# SCH_NFC-Card-Justin_2025-02-16.net
KiCad netlist of a schematic drawn in EasyEDA
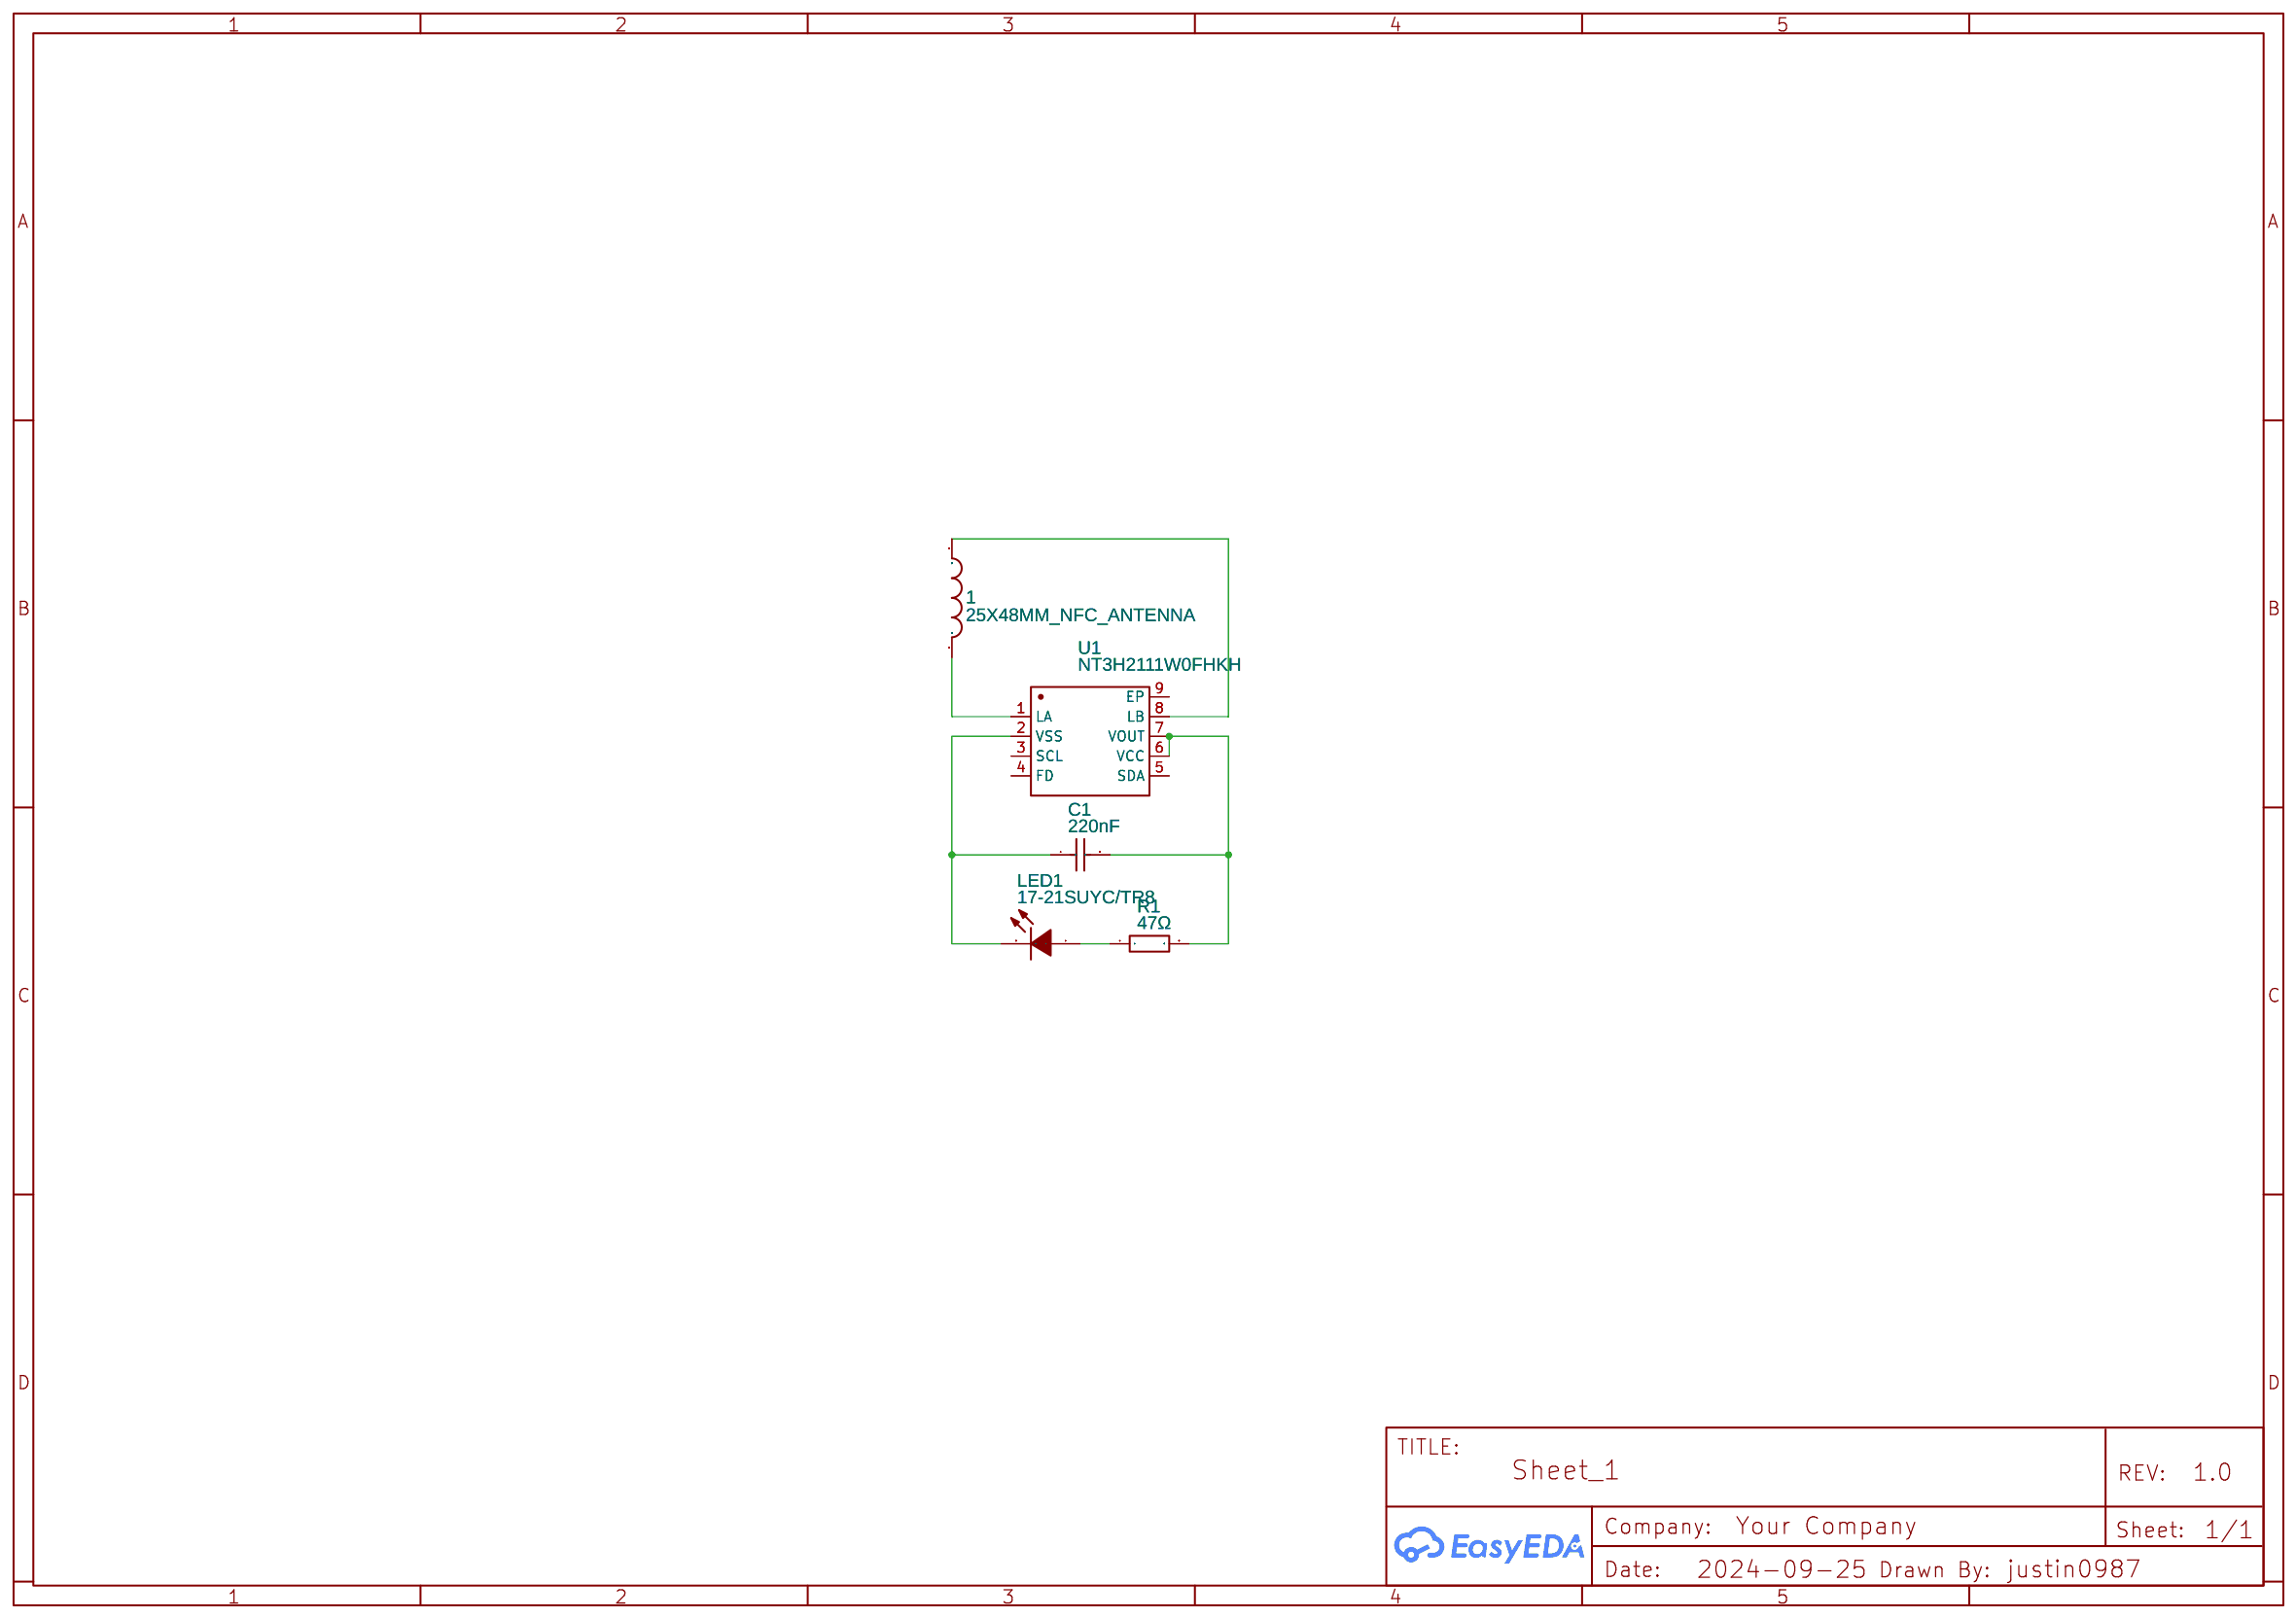
[diagram p0: schematic sheet]

(export (version "E")
  (design (tool "Eeschema 10.0.6"))
  (components
    (comp (ref "1") (value "25X48MM_NFC_ANTENNA") (libsource (lib "") (part "25X48MM_NFC_ANTENNA")))
    (comp (ref "C1")
      (value "220nF")
      (fields
        (field (name "Manufacturer Part") "CL10B224KA8NNNC")
        (field (name "Manufacturer") "SAMSUNG(三星)")
      )
      (libsource (lib "") (part "CL10B224KA8NNNC"))
    )
    (comp (ref "LED1")
      (value "17-21SUYC/TR8")
      (fields (field (name "Manufacturer Part") "KT-0805黄灯") (field (name "Manufacturer") "KENTO"))
      (libsource (lib "") (part "17-21SUYC/TR8"))
    )
    (comp (ref "R1")
      (value "47Ω")
      (fields
        (field (name "Manufacturer Part") "0603WAF470JT5E")
        (field (name "Manufacturer") "UNI-ROYAL(厚声)")
      )
      (libsource (lib "") (part "0603WAF470JT5E"))
    )
    (comp (ref "U1")
      (value "NT3H2111W0FHKH")
      (fields (field (name "Manufacturer") "NXP(恩智浦)"))
      (libsource (lib "") (part "NT3H2111W0FHKH"))
    )
  )
  (nets
    (net (code "1") (name "Net-(LED1-+)") (class "Default")
      (node (ref "LED1") (pin "1") (pinfunction "+_1") (pintype "unspecified"))
      (node (ref "R1") (pin "1") (pinfunction "1_1") (pintype "input"))
    )
    (net (code "2") (name "Net-(LED1--)") (class "Default")
      (node (ref "C1") (pin "1") (pinfunction "1_1") (pintype "input"))
      (node (ref "LED1") (pin "2") (pinfunction "-_2") (pintype "unspecified"))
      (node (ref "U1") (pin "2") (pinfunction "VSS_2") (pintype "unspecified"))
    )
    (net (code "3") (name "Net-(U1-LA)") (class "Default")
      (node (ref "1") (pin "P$2") (pinfunction "P$2_P$2") (pintype "bidirectional"))
      (node (ref "U1") (pin "1") (pinfunction "LA_1") (pintype "unspecified"))
    )
    (net (code "4") (name "Net-(U1-LB)") (class "Default")
      (node (ref "1") (pin "P$1") (pinfunction "P$1_P$1") (pintype "bidirectional"))
      (node (ref "U1") (pin "8") (pinfunction "LB_8") (pintype "unspecified"))
    )
    (net (code "5") (name "Net-(U1-VCC)") (class "Default")
      (node (ref "C1") (pin "2") (pinfunction "2_2") (pintype "input"))
      (node (ref "R1") (pin "2") (pinfunction "2_2") (pintype "input"))
      (node (ref "U1") (pin "6") (pinfunction "VCC_6") (pintype "unspecified"))
      (node (ref "U1") (pin "7") (pinfunction "VOUT_7") (pintype "unspecified"))
    )
    (net (code "6") (name "unconnected-(U1-EP-Pad9)") (class "Default")
      (node (ref "U1") (pin "9") (pinfunction "EP_9") (pintype "unspecified"))
    )
    (net (code "7") (name "unconnected-(U1-FD-Pad4)") (class "Default")
      (node (ref "U1") (pin "4") (pinfunction "FD_4") (pintype "unspecified"))
    )
    (net (code "8") (name "unconnected-(U1-SCL-Pad3)") (class "Default")
      (node (ref "U1") (pin "3") (pinfunction "SCL_3") (pintype "unspecified"))
    )
    (net (code "9") (name "unconnected-(U1-SDA-Pad5)") (class "Default")
      (node (ref "U1") (pin "5") (pinfunction "SDA_5") (pintype "unspecified"))
    )
  )
)
